# 01-PCIe.net
KiCad netlist of a schematic drawn in Altium Designer
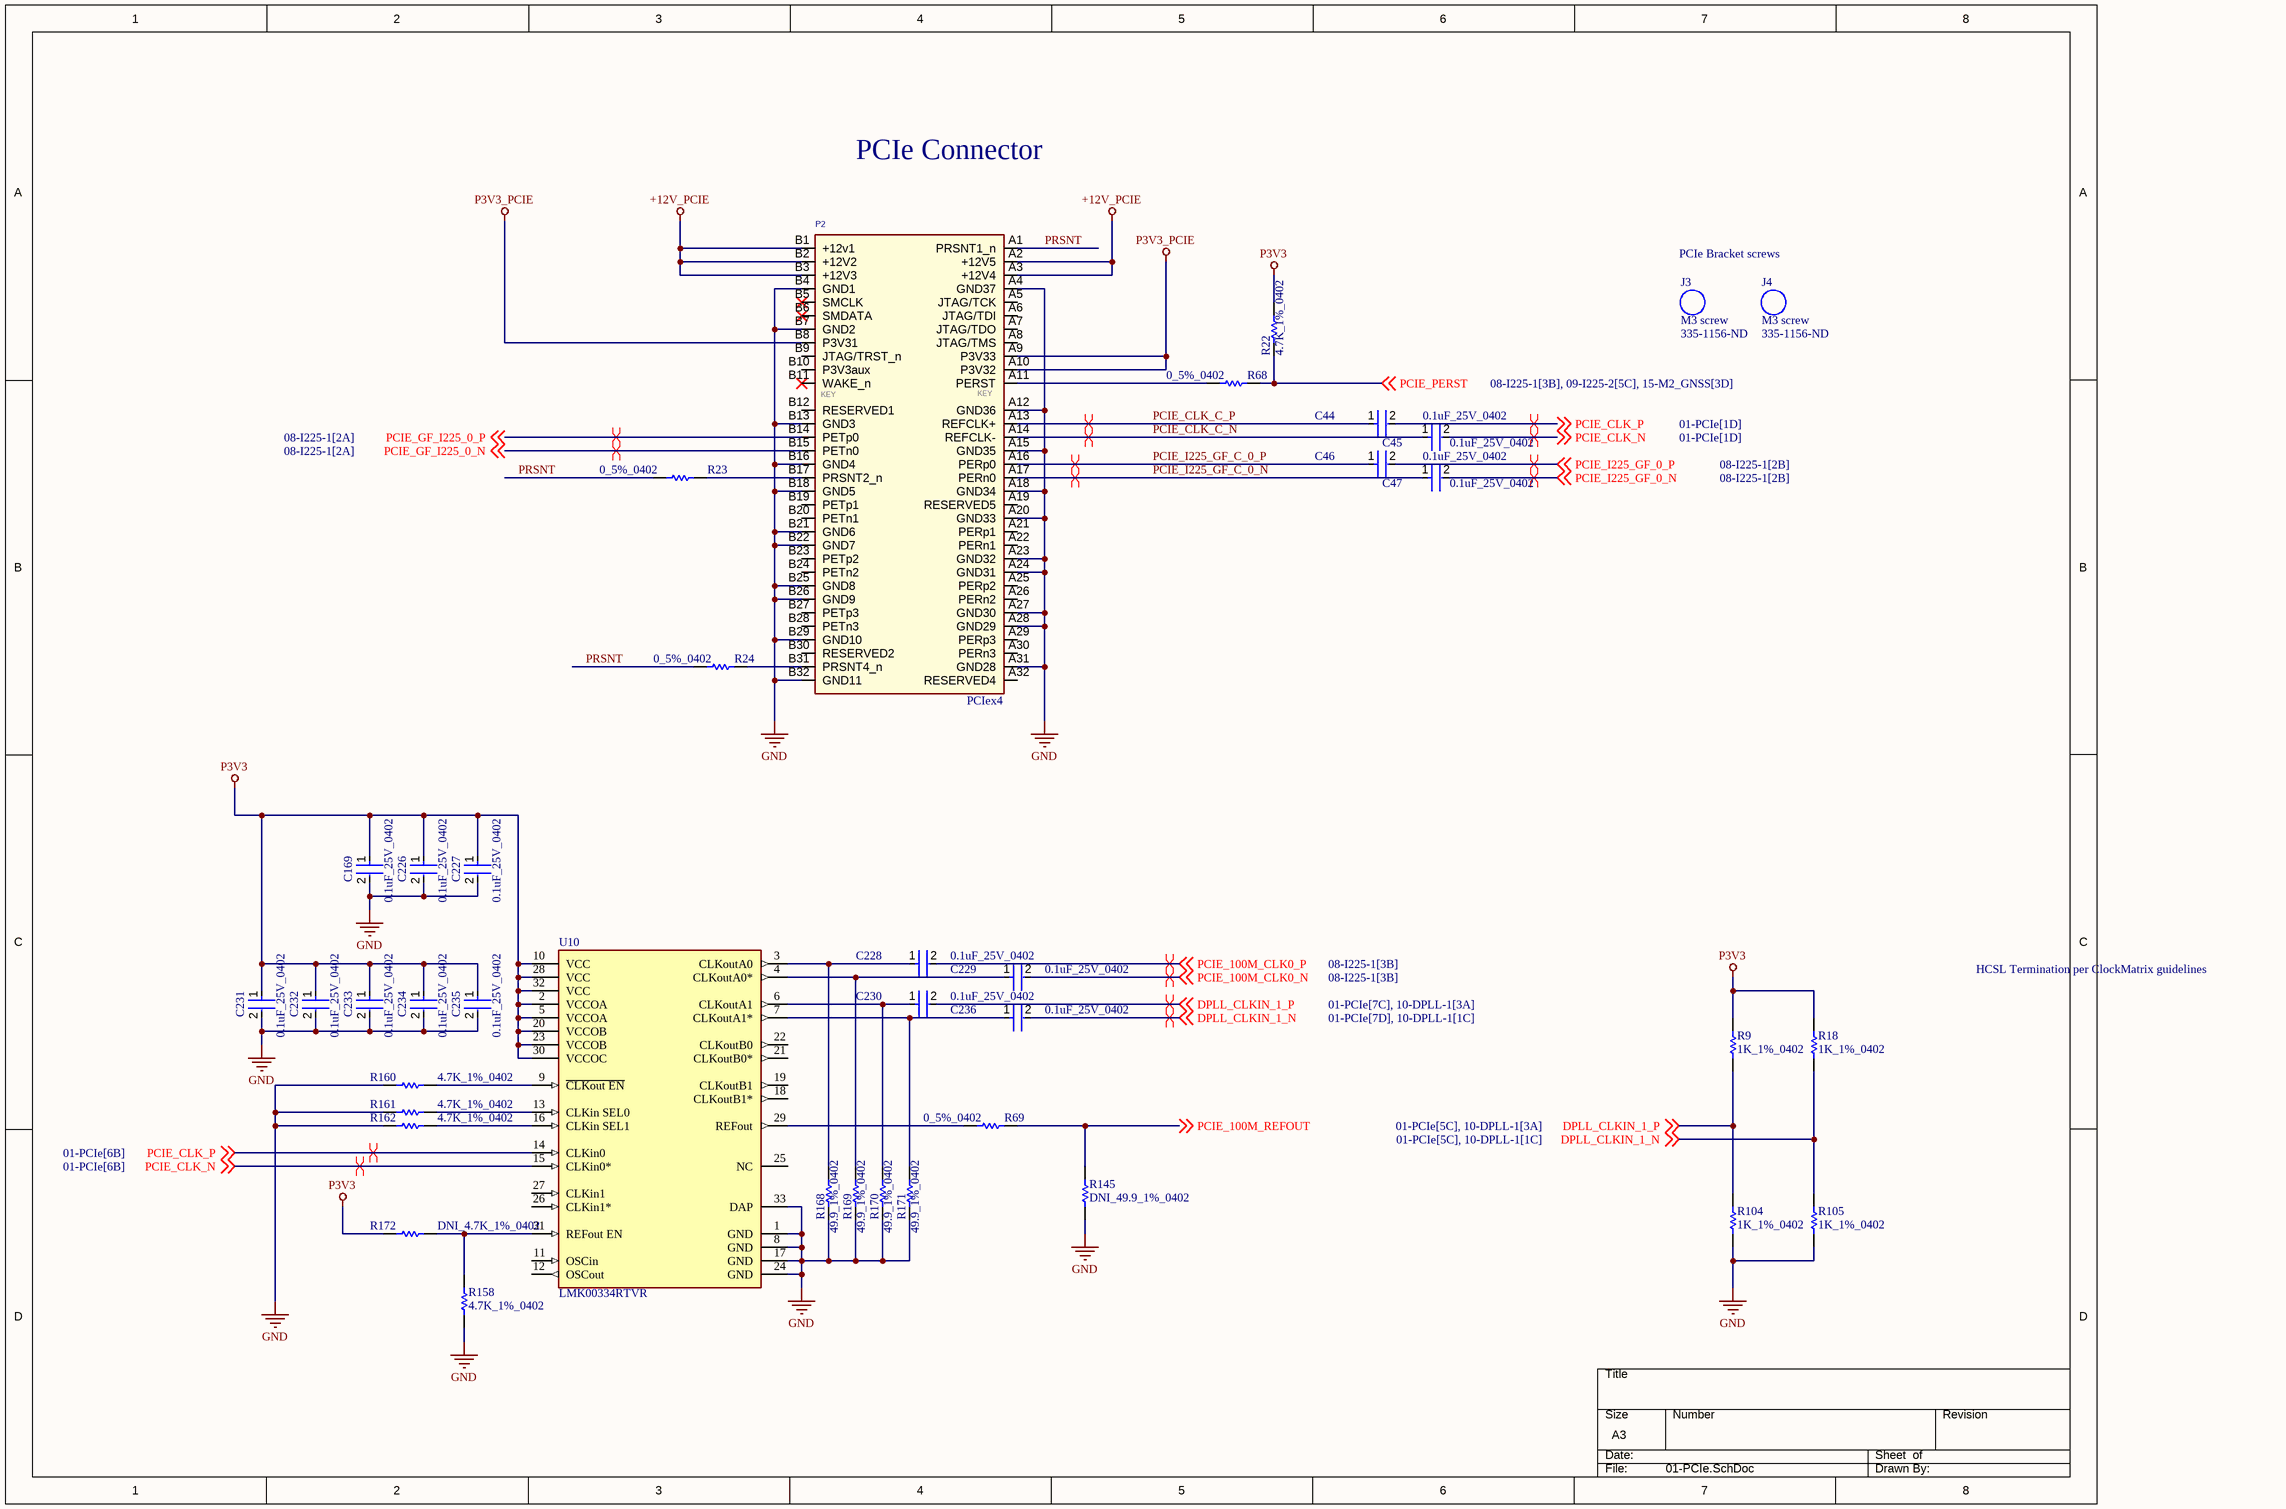
[diagram p0: 01-PCIe.SchDoc]

(export (version "E")
  (design (tool "Eeschema 10.0.6"))
  (components
    (comp (ref "C44")
      (value "0.1uF_25V_0402")
      (footprint "FP-0402-L_1_0_1-W_0_5_0_1-IPC_C")
      (description "General Purpose Ceramic Capacitor, 0402, 100nF, 10%, X7R, 15%, 25V")
      (fields (field (name "VOLTAGE") "25V") (field (name "TOLERANCE") "10%"))
      (libsource (lib "Altium Content Vault") (part "b4654b650e69147ec39a6b967a45e02"))
    )
    (comp (ref "C45")
      (value "0.1uF_25V_0402")
      (footprint "FP-0402-L_1_0_1-W_0_5_0_1-IPC_C")
      (description "General Purpose Ceramic Capacitor, 0402, 100nF, 10%, X7R, 15%, 25V")
      (fields (field (name "VOLTAGE") "25V") (field (name "TOLERANCE") "10%"))
      (libsource (lib "Altium Content Vault") (part "b4654b650e69147ec39a6b967a45e02"))
    )
    (comp (ref "C46")
      (value "0.1uF_25V_0402")
      (footprint "FP-0402-L_1_0_1-W_0_5_0_1-IPC_C")
      (description "General Purpose Ceramic Capacitor, 0402, 100nF, 10%, X7R, 15%, 25V")
      (fields (field (name "VOLTAGE") "25V") (field (name "TOLERANCE") "10%"))
      (libsource (lib "Altium Content Vault") (part "b4654b650e69147ec39a6b967a45e02"))
    )
    (comp (ref "C47")
      (value "0.1uF_25V_0402")
      (footprint "FP-0402-L_1_0_1-W_0_5_0_1-IPC_C")
      (description "General Purpose Ceramic Capacitor, 0402, 100nF, 10%, X7R, 15%, 25V")
      (fields (field (name "VOLTAGE") "25V") (field (name "TOLERANCE") "10%"))
      (libsource (lib "Altium Content Vault") (part "b4654b650e69147ec39a6b967a45e02"))
    )
    (comp (ref "C169")
      (value "0.1uF_25V_0402")
      (footprint "FP-0402-L_1_0_1-W_0_5_0_1-IPC_C")
      (description "General Purpose Ceramic Capacitor, 0402, 100nF, 10%, X7R, 15%, 25V")
      (fields (field (name "VOLTAGE") "25V") (field (name "TOLERANCE") "10%"))
      (libsource (lib "Altium Content Vault") (part "b4654b650e69147ec39a6b967a45e02"))
    )
    (comp (ref "C226")
      (value "0.1uF_25V_0402")
      (footprint "FP-0402-L_1_0_1-W_0_5_0_1-IPC_C")
      (description "General Purpose Ceramic Capacitor, 0402, 100nF, 10%, X7R, 15%, 25V")
      (fields (field (name "VOLTAGE") "25V") (field (name "TOLERANCE") "10%"))
      (libsource (lib "Altium Content Vault") (part "b4654b650e69147ec39a6b967a45e02"))
    )
    (comp (ref "C227")
      (value "0.1uF_25V_0402")
      (footprint "FP-0402-L_1_0_1-W_0_5_0_1-IPC_C")
      (description "General Purpose Ceramic Capacitor, 0402, 100nF, 10%, X7R, 15%, 25V")
      (fields (field (name "VOLTAGE") "25V") (field (name "TOLERANCE") "10%"))
      (libsource (lib "Altium Content Vault") (part "b4654b650e69147ec39a6b967a45e02"))
    )
    (comp (ref "C228")
      (value "0.1uF_25V_0402")
      (footprint "FP-0402-L_1_0_1-W_0_5_0_1-IPC_C")
      (description "General Purpose Ceramic Capacitor, 0402, 100nF, 10%, X7R, 15%, 25V")
      (fields (field (name "VOLTAGE") "25V") (field (name "TOLERANCE") "10%"))
      (libsource (lib "Altium Content Vault") (part "b4654b650e69147ec39a6b967a45e02"))
    )
    (comp (ref "C229")
      (value "0.1uF_25V_0402")
      (footprint "FP-0402-L_1_0_1-W_0_5_0_1-IPC_C")
      (description "General Purpose Ceramic Capacitor, 0402, 100nF, 10%, X7R, 15%, 25V")
      (fields (field (name "VOLTAGE") "25V") (field (name "TOLERANCE") "10%"))
      (libsource (lib "Altium Content Vault") (part "b4654b650e69147ec39a6b967a45e02"))
    )
    (comp (ref "C230")
      (value "0.1uF_25V_0402")
      (footprint "FP-0402-L_1_0_1-W_0_5_0_1-IPC_C")
      (description "General Purpose Ceramic Capacitor, 0402, 100nF, 10%, X7R, 15%, 25V")
      (fields (field (name "VOLTAGE") "25V") (field (name "TOLERANCE") "10%"))
      (libsource (lib "Altium Content Vault") (part "b4654b650e69147ec39a6b967a45e02"))
    )
    (comp (ref "C231")
      (value "0.1uF_25V_0402")
      (footprint "FP-0402-L_1_0_1-W_0_5_0_1-IPC_C")
      (description "General Purpose Ceramic Capacitor, 0402, 100nF, 10%, X7R, 15%, 25V")
      (fields (field (name "VOLTAGE") "25V") (field (name "TOLERANCE") "10%"))
      (libsource (lib "Altium Content Vault") (part "b4654b650e69147ec39a6b967a45e02"))
    )
    (comp (ref "C232")
      (value "0.1uF_25V_0402")
      (footprint "FP-0402-L_1_0_1-W_0_5_0_1-IPC_C")
      (description "General Purpose Ceramic Capacitor, 0402, 100nF, 10%, X7R, 15%, 25V")
      (fields (field (name "VOLTAGE") "25V") (field (name "TOLERANCE") "10%"))
      (libsource (lib "Altium Content Vault") (part "b4654b650e69147ec39a6b967a45e02"))
    )
    (comp (ref "C233")
      (value "0.1uF_25V_0402")
      (footprint "FP-0402-L_1_0_1-W_0_5_0_1-IPC_C")
      (description "General Purpose Ceramic Capacitor, 0402, 100nF, 10%, X7R, 15%, 25V")
      (fields (field (name "VOLTAGE") "25V") (field (name "TOLERANCE") "10%"))
      (libsource (lib "Altium Content Vault") (part "b4654b650e69147ec39a6b967a45e02"))
    )
    (comp (ref "C234")
      (value "0.1uF_25V_0402")
      (footprint "FP-0402-L_1_0_1-W_0_5_0_1-IPC_C")
      (description "General Purpose Ceramic Capacitor, 0402, 100nF, 10%, X7R, 15%, 25V")
      (fields (field (name "VOLTAGE") "25V") (field (name "TOLERANCE") "10%"))
      (libsource (lib "Altium Content Vault") (part "b4654b650e69147ec39a6b967a45e02"))
    )
    (comp (ref "C235")
      (value "0.1uF_25V_0402")
      (footprint "FP-0402-L_1_0_1-W_0_5_0_1-IPC_C")
      (description "General Purpose Ceramic Capacitor, 0402, 100nF, 10%, X7R, 15%, 25V")
      (fields (field (name "VOLTAGE") "25V") (field (name "TOLERANCE") "10%"))
      (libsource (lib "Altium Content Vault") (part "b4654b650e69147ec39a6b967a45e02"))
    )
    (comp (ref "C236")
      (value "0.1uF_25V_0402")
      (footprint "FP-0402-L_1_0_1-W_0_5_0_1-IPC_C")
      (description "General Purpose Ceramic Capacitor, 0402, 100nF, 10%, X7R, 15%, 25V")
      (fields (field (name "VOLTAGE") "25V") (field (name "TOLERANCE") "10%"))
      (libsource (lib "Altium Content Vault") (part "b4654b650e69147ec39a6b967a45e02"))
    )
    (comp (ref "J3")
      (value "M3 screw")
      (fields (field (name "SUPPLIER PART NUMBER 1") "335-1156-ND"))
      (libsource (lib "FPGA_CONN") (part "M3 screw"))
    )
    (comp (ref "J4")
      (value "M3 screw")
      (fields (field (name "SUPPLIER PART NUMBER 1") "335-1156-ND"))
      (libsource (lib "FPGA_CONN") (part "M3 screw"))
    )
    (comp (ref "P2")
      (value "PCIex4")
      (footprint "PCIE_4LANE_EDGE")
      (description "PCIE x4 Edge Connector,OrCAD Symbol,NC")
      (fields (field (name "PART NUMBER") "451") (field (name "MANUFACTURER") "NA"))
      (libsource (lib "Connectors") (part "PCIex4"))
    )
    (comp (ref "R9")
      (value "1K_1%_0402")
      (footprint "RESC1005X40X25NL05T05")
      (fields (field (name "MANUFACTURER") "Vishay Dale") (field (name "PART NUMBER") "CRCW04021K00FKTD"))
      (libsource (lib "Altium Content Vault") (part "RES"))
    )
    (comp (ref "R18")
      (value "1K_1%_0402")
      (footprint "RESC1005X40X25NL05T05")
      (fields (field (name "MANUFACTURER") "Vishay Dale") (field (name "PART NUMBER") "CRCW04021K00FKTD"))
      (libsource (lib "Altium Content Vault") (part "RES"))
    )
    (comp (ref "R22")
      (value "4.7K_1%_0402")
      (footprint "RESC1005X40X25NL10T10")
      (fields (field (name "MANUFACTURER") "Bourns") (field (name "PART NUMBER") "CR0402-FX-4701GLF"))
      (libsource (lib "Altium Content Vault") (part "RES"))
    )
    (comp (ref "R23")
      (value "0_5%_0402")
      (footprint "RESC1005X40X25LL10T10")
      (fields (field (name "MANUFACTURER") "KOA Speer") (field (name "PART NUMBER") "RK73Z1ETTP"))
      (libsource (lib "Altium Content Vault") (part "RES"))
    )
    (comp (ref "R24")
      (value "0_5%_0402")
      (footprint "RESC1005X40X25LL10T10")
      (fields (field (name "MANUFACTURER") "KOA Speer") (field (name "PART NUMBER") "RK73Z1ETTP"))
      (libsource (lib "Altium Content Vault") (part "RES"))
    )
    (comp (ref "R68")
      (value "0_5%_0402")
      (footprint "RESC1005X40X25LL10T10")
      (fields (field (name "MANUFACTURER") "KOA Speer") (field (name "PART NUMBER") "RK73Z1ETTP"))
      (libsource (lib "Altium Content Vault") (part "RES"))
    )
    (comp (ref "R69")
      (value "0_5%_0402")
      (footprint "RESC1005X40X25LL10T10")
      (fields (field (name "MANUFACTURER") "KOA Speer") (field (name "PART NUMBER") "RK73Z1ETTP"))
      (libsource (lib "Altium Content Vault") (part "RES"))
    )
    (comp (ref "R104")
      (value "1K_1%_0402")
      (footprint "RESC1005X40X25NL05T05")
      (fields (field (name "MANUFACTURER") "Vishay Dale") (field (name "PART NUMBER") "CRCW04021K00FKTD"))
      (libsource (lib "Altium Content Vault") (part "RES"))
    )
    (comp (ref "R105")
      (value "1K_1%_0402")
      (footprint "RESC1005X40X25NL05T05")
      (fields (field (name "MANUFACTURER") "Vishay Dale") (field (name "PART NUMBER") "CRCW04021K00FKTD"))
      (libsource (lib "Altium Content Vault") (part "RES"))
    )
    (comp (ref "R145")
      (value "DNI_49.9_1%_0402")
      (footprint "RESC1005X40X25NL10T10")
      (fields (field (name "PART NUMBER") "RK73H1ETTP49R9F") (field (name "MANUFACTURER") "KOA Speer"))
      (libsource (lib "Altium Content Vault") (part "RES"))
    )
    (comp (ref "R158")
      (value "4.7K_1%_0402")
      (footprint "RESC1005X40X25NL10T10")
      (fields (field (name "MANUFACTURER") "Bourns") (field (name "PART NUMBER") "CR0402-FX-4701GLF"))
      (libsource (lib "Altium Content Vault") (part "RES"))
    )
    (comp (ref "R160")
      (value "4.7K_1%_0402")
      (footprint "RESC1005X40X25NL10T10")
      (fields (field (name "MANUFACTURER") "Bourns") (field (name "PART NUMBER") "CR0402-FX-4701GLF"))
      (libsource (lib "Altium Content Vault") (part "RES"))
    )
    (comp (ref "R161")
      (value "4.7K_1%_0402")
      (footprint "RESC1005X40X25NL10T10")
      (fields (field (name "MANUFACTURER") "Bourns") (field (name "PART NUMBER") "CR0402-FX-4701GLF"))
      (libsource (lib "Altium Content Vault") (part "RES"))
    )
    (comp (ref "R162")
      (value "4.7K_1%_0402")
      (footprint "RESC1005X40X25NL10T10")
      (fields (field (name "MANUFACTURER") "Bourns") (field (name "PART NUMBER") "CR0402-FX-4701GLF"))
      (libsource (lib "Altium Content Vault") (part "RES"))
    )
    (comp (ref "R168")
      (value "49.9_1%_0402")
      (footprint "RESC1005X40X25NL10T10")
      (fields (field (name "PART NUMBER") "RK73H1ETTP49R9F") (field (name "MANUFACTURER") "KOA Speer"))
      (libsource (lib "Altium Content Vault") (part "RES"))
    )
    (comp (ref "R169")
      (value "49.9_1%_0402")
      (footprint "RESC1005X40X25NL10T10")
      (fields (field (name "PART NUMBER") "RK73H1ETTP49R9F") (field (name "MANUFACTURER") "KOA Speer"))
      (libsource (lib "Altium Content Vault") (part "RES"))
    )
    (comp (ref "R170")
      (value "49.9_1%_0402")
      (footprint "RESC1005X40X25NL10T10")
      (fields (field (name "PART NUMBER") "RK73H1ETTP49R9F") (field (name "MANUFACTURER") "KOA Speer"))
      (libsource (lib "Altium Content Vault") (part "RES"))
    )
    (comp (ref "R171")
      (value "49.9_1%_0402")
      (footprint "RESC1005X40X25NL10T10")
      (fields (field (name "PART NUMBER") "RK73H1ETTP49R9F") (field (name "MANUFACTURER") "KOA Speer"))
      (libsource (lib "Altium Content Vault") (part "RES"))
    )
    (comp (ref "R172")
      (value "DNI_4.7K_1%_0402")
      (footprint "RESC1005X40X25NL10T10")
      (fields (field (name "MANUFACTURER") "Bourns") (field (name "PART NUMBER") "CR0402-FX-4701GLF"))
      (libsource (lib "Altium Content Vault") (part "RES"))
    )
    (comp (ref "U10")
      (value "LMK00334RTVR")
      (footprint "FP-RTV0032A-MFG")
      (description "IC CLK BUF 400MHZ 1CIRC 32WQFN")
      (libsource (lib "Altium Content Vault") (part "b0788d09999557299357136416a342e"))
    )
  )
  (nets
    (net (code "1") (name "+12V_PCIE") (class "Default")
      (node (ref "P2") (pin "A2") (pinfunction "+12V5_A2") (pintype "passive"))
      (node (ref "P2") (pin "A3") (pinfunction "+12V4_A3") (pintype "passive"))
      (node (ref "P2") (pin "B1") (pinfunction "+12v1_B1") (pintype "power_in"))
      (node (ref "P2") (pin "B2") (pinfunction "+12V2_B2") (pintype "power_in"))
      (node (ref "P2") (pin "B3") (pinfunction "+12V3_B3") (pintype "power_in"))
    )
    (net (code "2") (name "/PCIE_CLK_C_N") (class "Default")
      (node (ref "C45") (pin "1") (pinfunction "1_1") (pintype "passive"))
      (node (ref "P2") (pin "A14") (pinfunction "REFCLK-_A14") (pintype "passive"))
    )
    (net (code "3") (name "/PCIE_CLK_C_P") (class "Default")
      (node (ref "C44") (pin "1") (pinfunction "1_1") (pintype "passive"))
      (node (ref "P2") (pin "A13") (pinfunction "REFCLK+_A13") (pintype "passive"))
    )
    (net (code "4") (name "/PCIE_I225_GF_C_0_N") (class "Default")
      (node (ref "C47") (pin "1") (pinfunction "1_1") (pintype "passive"))
      (node (ref "P2") (pin "A17") (pinfunction "PERn0_A17") (pintype "passive"))
    )
    (net (code "5") (name "/PCIE_I225_GF_C_0_P") (class "Default")
      (node (ref "C46") (pin "1") (pinfunction "1_1") (pintype "passive"))
      (node (ref "P2") (pin "A16") (pinfunction "PERp0_A16") (pintype "passive"))
    )
    (net (code "6") (name "/PRSNT") (class "Default")
      (node (ref "P2") (pin "A1") (pinfunction "PRSNT1_n_A1") (pintype "passive"))
      (node (ref "R23") (pin "1") (pinfunction "1_1") (pintype "passive"))
      (node (ref "R24") (pin "1") (pinfunction "1_1") (pintype "passive"))
    )
    (net (code "7") (name "DPLL_CLKIN_1_N") (class "Default")
      (node (ref "C236") (pin "2") (pinfunction "2_2") (pintype "passive"))
      (node (ref "R105") (pin "2") (pinfunction "2_2") (pintype "passive"))
      (node (ref "R18") (pin "1") (pinfunction "1_1") (pintype "passive"))
    )
    (net (code "8") (name "DPLL_CLKIN_1_P") (class "Default")
      (node (ref "C230") (pin "2") (pinfunction "2_2") (pintype "passive"))
      (node (ref "R104") (pin "2") (pinfunction "2_2") (pintype "passive"))
      (node (ref "R9") (pin "1") (pinfunction "1_1") (pintype "passive"))
    )
    (net (code "9") (name "GND") (class "Default")
      (node (ref "C169") (pin "2") (pinfunction "2_2") (pintype "passive"))
      (node (ref "C226") (pin "2") (pinfunction "2_2") (pintype "passive"))
      (node (ref "C227") (pin "2") (pinfunction "2_2") (pintype "passive"))
      (node (ref "C231") (pin "2") (pinfunction "2_2") (pintype "passive"))
      (node (ref "C232") (pin "2") (pinfunction "2_2") (pintype "passive"))
      (node (ref "C233") (pin "2") (pinfunction "2_2") (pintype "passive"))
      (node (ref "C234") (pin "2") (pinfunction "2_2") (pintype "passive"))
      (node (ref "C235") (pin "2") (pinfunction "2_2") (pintype "passive"))
      (node (ref "P2") (pin "A12") (pinfunction "GND36_A12") (pintype "power_in"))
      (node (ref "P2") (pin "A15") (pinfunction "GND35_A15") (pintype "power_in"))
      (node (ref "P2") (pin "A18") (pinfunction "GND34_A18") (pintype "power_in"))
      (node (ref "P2") (pin "A20") (pinfunction "GND33_A20") (pintype "power_in"))
      (node (ref "P2") (pin "A23") (pinfunction "GND32_A23") (pintype "power_in"))
      (node (ref "P2") (pin "A24") (pinfunction "GND31_A24") (pintype "power_in"))
      (node (ref "P2") (pin "A27") (pinfunction "GND30_A27") (pintype "power_in"))
      (node (ref "P2") (pin "A28") (pinfunction "GND29_A28") (pintype "power_in"))
      (node (ref "P2") (pin "A31") (pinfunction "GND28_A31") (pintype "power_in"))
      (node (ref "P2") (pin "A4") (pinfunction "GND37_A4") (pintype "power_in"))
      (node (ref "P2") (pin "B13") (pinfunction "GND3_B13") (pintype "power_in"))
      (node (ref "P2") (pin "B16") (pinfunction "GND4_B16") (pintype "power_in"))
      (node (ref "P2") (pin "B18") (pinfunction "GND5_B18") (pintype "power_in"))
      (node (ref "P2") (pin "B21") (pinfunction "GND6_B21") (pintype "power_in"))
      (node (ref "P2") (pin "B22") (pinfunction "GND7_B22") (pintype "power_in"))
      (node (ref "P2") (pin "B25") (pinfunction "GND8_B25") (pintype "power_in"))
      (node (ref "P2") (pin "B26") (pinfunction "GND9_B26") (pintype "power_in"))
      (node (ref "P2") (pin "B29") (pinfunction "GND10_B29") (pintype "power_in"))
      (node (ref "P2") (pin "B32") (pinfunction "GND11_B32") (pintype "power_in"))
      (node (ref "P2") (pin "B4") (pinfunction "GND1_B4") (pintype "power_in"))
      (node (ref "P2") (pin "B7") (pinfunction "GND2_B7") (pintype "power_in"))
      (node (ref "R104") (pin "1") (pinfunction "1_1") (pintype "passive"))
      (node (ref "R105") (pin "1") (pinfunction "1_1") (pintype "passive"))
      (node (ref "R145") (pin "2") (pinfunction "2_2") (pintype "passive"))
      (node (ref "R158") (pin "2") (pinfunction "2_2") (pintype "passive"))
      (node (ref "R160") (pin "2") (pinfunction "2_2") (pintype "passive"))
      (node (ref "R161") (pin "2") (pinfunction "2_2") (pintype "passive"))
      (node (ref "R162") (pin "2") (pinfunction "2_2") (pintype "passive"))
      (node (ref "R168") (pin "1") (pinfunction "1_1") (pintype "passive"))
      (node (ref "R169") (pin "1") (pinfunction "1_1") (pintype "passive"))
      (node (ref "R170") (pin "1") (pinfunction "1_1") (pintype "passive"))
      (node (ref "R171") (pin "1") (pinfunction "1_1") (pintype "passive"))
      (node (ref "U10") (pin "1") (pinfunction "GND_1") (pintype "power_in"))
      (node (ref "U10") (pin "17") (pinfunction "GND_17") (pintype "power_in"))
      (node (ref "U10") (pin "24") (pinfunction "GND_24") (pintype "power_in"))
      (node (ref "U10") (pin "33") (pinfunction "DAP_33") (pintype "power_in"))
      (node (ref "U10") (pin "8") (pinfunction "GND_8") (pintype "power_in"))
    )
    (net (code "10") (name "Net-(P2-PERST)") (class "Default")
      (node (ref "P2") (pin "A11") (pinfunction "PERST_A11") (pintype "passive"))
      (node (ref "R68") (pin "1") (pinfunction "1_1") (pintype "passive"))
    )
    (net (code "11") (name "Net-(P2-PRSNT2_n)") (class "Default")
      (node (ref "P2") (pin "B17") (pinfunction "PRSNT2_n_B17") (pintype "passive"))
      (node (ref "R23") (pin "2") (pinfunction "2_2") (pintype "passive"))
    )
    (net (code "12") (name "Net-(P2-PRSNT4_n)") (class "Default")
      (node (ref "P2") (pin "B31") (pinfunction "PRSNT4_n_B31") (pintype "passive"))
      (node (ref "R24") (pin "2") (pinfunction "2_2") (pintype "passive"))
    )
    (net (code "13") (name "Net-(U10-CLKin_SEL0)") (class "Default")
      (node (ref "R161") (pin "1") (pinfunction "1_1") (pintype "passive"))
      (node (ref "U10") (pin "13") (pinfunction "CLKin_SEL0_13") (pintype "input"))
    )
    (net (code "14") (name "Net-(U10-CLKin_SEL1)") (class "Default")
      (node (ref "R162") (pin "1") (pinfunction "1_1") (pintype "passive"))
      (node (ref "U10") (pin "16") (pinfunction "CLKin_SEL1_16") (pintype "input"))
    )
    (net (code "15") (name "Net-(U10-CLKoutA0)") (class "Default")
      (node (ref "C228") (pin "1") (pinfunction "1_1") (pintype "passive"))
      (node (ref "R168") (pin "2") (pinfunction "2_2") (pintype "passive"))
      (node (ref "U10") (pin "3") (pinfunction "CLKoutA0_3") (pintype "output"))
    )
    (net (code "16") (name "Net-(U10-CLKoutA0*)") (class "Default")
      (node (ref "C229") (pin "1") (pinfunction "1_1") (pintype "passive"))
      (node (ref "R169") (pin "2") (pinfunction "2_2") (pintype "passive"))
      (node (ref "U10") (pin "4") (pinfunction "CLKoutA0*_4") (pintype "output"))
    )
    (net (code "17") (name "Net-(U10-CLKoutA1)") (class "Default")
      (node (ref "C230") (pin "1") (pinfunction "1_1") (pintype "passive"))
      (node (ref "R170") (pin "2") (pinfunction "2_2") (pintype "passive"))
      (node (ref "U10") (pin "6") (pinfunction "CLKoutA1_6") (pintype "output"))
    )
    (net (code "18") (name "Net-(U10-CLKoutA1*)") (class "Default")
      (node (ref "C236") (pin "1") (pinfunction "1_1") (pintype "passive"))
      (node (ref "R171") (pin "2") (pinfunction "2_2") (pintype "passive"))
      (node (ref "U10") (pin "7") (pinfunction "CLKoutA1*_7") (pintype "output"))
    )
    (net (code "19") (name "Net-(U10-REFout)") (class "Default")
      (node (ref "R69") (pin "1") (pinfunction "1_1") (pintype "passive"))
      (node (ref "U10") (pin "29") (pinfunction "REFout_29") (pintype "output"))
    )
    (net (code "20") (name "Net-(U10-REFout_EN)") (class "Default")
      (node (ref "R158") (pin "1") (pinfunction "1_1") (pintype "passive"))
      (node (ref "R172") (pin "1") (pinfunction "1_1") (pintype "passive"))
      (node (ref "U10") (pin "31") (pinfunction "REFout_EN_31") (pintype "input"))
    )
    (net (code "21") (name "Net-(U10-~{CLKout_EN})") (class "Default")
      (node (ref "R160") (pin "1") (pinfunction "1_1") (pintype "passive"))
      (node (ref "U10") (pin "9") (pinfunction "~{CLKout_EN}_9") (pintype "input"))
    )
    (net (code "22") (name "P3V3") (class "Default")
      (node (ref "C169") (pin "1") (pinfunction "1_1") (pintype "passive"))
      (node (ref "C226") (pin "1") (pinfunction "1_1") (pintype "passive"))
      (node (ref "C227") (pin "1") (pinfunction "1_1") (pintype "passive"))
      (node (ref "C231") (pin "1") (pinfunction "1_1") (pintype "passive"))
      (node (ref "C232") (pin "1") (pinfunction "1_1") (pintype "passive"))
      (node (ref "C233") (pin "1") (pinfunction "1_1") (pintype "passive"))
      (node (ref "C234") (pin "1") (pinfunction "1_1") (pintype "passive"))
      (node (ref "C235") (pin "1") (pinfunction "1_1") (pintype "passive"))
      (node (ref "R172") (pin "2") (pinfunction "2_2") (pintype "passive"))
      (node (ref "R18") (pin "2") (pinfunction "2_2") (pintype "passive"))
      (node (ref "R22") (pin "2") (pinfunction "2_2") (pintype "passive"))
      (node (ref "R9") (pin "2") (pinfunction "2_2") (pintype "passive"))
      (node (ref "U10") (pin "10") (pinfunction "VCC_10") (pintype "power_in"))
      (node (ref "U10") (pin "2") (pinfunction "VCCOA_2") (pintype "power_in"))
      (node (ref "U10") (pin "20") (pinfunction "VCCOB_20") (pintype "power_in"))
      (node (ref "U10") (pin "23") (pinfunction "VCCOB_23") (pintype "power_in"))
      (node (ref "U10") (pin "28") (pinfunction "VCC_28") (pintype "power_in"))
      (node (ref "U10") (pin "30") (pinfunction "VCCOC_30") (pintype "power_in"))
      (node (ref "U10") (pin "32") (pinfunction "VCC_32") (pintype "power_in"))
      (node (ref "U10") (pin "5") (pinfunction "VCCOA_5") (pintype "power_in"))
    )
    (net (code "23") (name "P3V3_PCIE") (class "Default")
      (node (ref "P2") (pin "A10") (pinfunction "P3V32_A10") (pintype "passive"))
      (node (ref "P2") (pin "A9") (pinfunction "P3V33_A9") (pintype "passive"))
      (node (ref "P2") (pin "B8") (pinfunction "P3V31_B8") (pintype "power_in"))
    )
    (net (code "24") (name "PCIE_100M_CLK0_N") (class "Default")
      (node (ref "C229") (pin "2") (pinfunction "2_2") (pintype "passive"))
    )
    (net (code "25") (name "PCIE_100M_CLK0_P") (class "Default")
      (node (ref "C228") (pin "2") (pinfunction "2_2") (pintype "passive"))
    )
    (net (code "26") (name "PCIE_100M_REFOUT") (class "Default")
      (node (ref "R145") (pin "1") (pinfunction "1_1") (pintype "passive"))
      (node (ref "R69") (pin "2") (pinfunction "2_2") (pintype "passive"))
    )
    (net (code "27") (name "PCIE_CLK_N") (class "Default")
      (node (ref "C45") (pin "2") (pinfunction "2_2") (pintype "passive"))
      (node (ref "U10") (pin "15") (pinfunction "CLKin0*_15") (pintype "input"))
    )
    (net (code "28") (name "PCIE_CLK_P") (class "Default")
      (node (ref "C44") (pin "2") (pinfunction "2_2") (pintype "passive"))
      (node (ref "U10") (pin "14") (pinfunction "CLKin0_14") (pintype "input"))
    )
    (net (code "29") (name "PCIE_GF_I225_0_N") (class "Default")
      (node (ref "P2") (pin "B15") (pinfunction "PETn0_B15") (pintype "passive"))
    )
    (net (code "30") (name "PCIE_GF_I225_0_P") (class "Default")
      (node (ref "P2") (pin "B14") (pinfunction "PETp0_B14") (pintype "passive"))
    )
    (net (code "31") (name "PCIE_I225_GF_0_N") (class "Default")
      (node (ref "C47") (pin "2") (pinfunction "2_2") (pintype "passive"))
    )
    (net (code "32") (name "PCIE_I225_GF_0_P") (class "Default")
      (node (ref "C46") (pin "2") (pinfunction "2_2") (pintype "passive"))
    )
    (net (code "33") (name "PCIE_PERST") (class "Default")
      (node (ref "R22") (pin "1") (pinfunction "1_1") (pintype "passive"))
      (node (ref "R68") (pin "2") (pinfunction "2_2") (pintype "passive"))
    )
    (net (code "34") (name "unconnected-(P2-JTAG{slash}TCK-PadA5)") (class "Default")
      (node (ref "P2") (pin "A5") (pinfunction "JTAG/TCK_A5") (pintype "passive"))
    )
    (net (code "35") (name "unconnected-(P2-JTAG{slash}TDI-PadA6)") (class "Default")
      (node (ref "P2") (pin "A6") (pinfunction "JTAG/TDI_A6") (pintype "passive"))
    )
    (net (code "36") (name "unconnected-(P2-JTAG{slash}TDO-PadA7)") (class "Default")
      (node (ref "P2") (pin "A7") (pinfunction "JTAG/TDO_A7") (pintype "passive"))
    )
    (net (code "37") (name "unconnected-(P2-JTAG{slash}TMS-PadA8)") (class "Default")
      (node (ref "P2") (pin "A8") (pinfunction "JTAG/TMS_A8") (pintype "passive"))
    )
    (net (code "38") (name "unconnected-(P2-JTAG{slash}TRST_n-PadB9)") (class "Default")
      (node (ref "P2") (pin "B9") (pinfunction "JTAG/TRST_n_B9") (pintype "passive"))
    )
    (net (code "39") (name "unconnected-(P2-P3V3aux-PadB10)") (class "Default")
      (node (ref "P2") (pin "B10") (pinfunction "P3V3aux_B10") (pintype "passive"))
    )
    (net (code "40") (name "unconnected-(P2-PERn1-PadA22)") (class "Default")
      (node (ref "P2") (pin "A22") (pinfunction "PERn1_A22") (pintype "passive"))
    )
    (net (code "41") (name "unconnected-(P2-PERn2-PadA26)") (class "Default")
      (node (ref "P2") (pin "A26") (pinfunction "PERn2_A26") (pintype "passive"))
    )
    (net (code "42") (name "unconnected-(P2-PERn3-PadA30)") (class "Default")
      (node (ref "P2") (pin "A30") (pinfunction "PERn3_A30") (pintype "passive"))
    )
    (net (code "43") (name "unconnected-(P2-PERp1-PadA21)") (class "Default")
      (node (ref "P2") (pin "A21") (pinfunction "PERp1_A21") (pintype "passive"))
    )
    (net (code "44") (name "unconnected-(P2-PERp2-PadA25)") (class "Default")
      (node (ref "P2") (pin "A25") (pinfunction "PERp2_A25") (pintype "passive"))
    )
    (net (code "45") (name "unconnected-(P2-PERp3-PadA29)") (class "Default")
      (node (ref "P2") (pin "A29") (pinfunction "PERp3_A29") (pintype "passive"))
    )
    (net (code "46") (name "unconnected-(P2-PETn1-PadB20)") (class "Default")
      (node (ref "P2") (pin "B20") (pinfunction "PETn1_B20") (pintype "passive"))
    )
    (net (code "47") (name "unconnected-(P2-PETn2-PadB24)") (class "Default")
      (node (ref "P2") (pin "B24") (pinfunction "PETn2_B24") (pintype "passive"))
    )
    (net (code "48") (name "unconnected-(P2-PETn3-PadB28)") (class "Default")
      (node (ref "P2") (pin "B28") (pinfunction "PETn3_B28") (pintype "passive"))
    )
    (net (code "49") (name "unconnected-(P2-PETp1-PadB19)") (class "Default")
      (node (ref "P2") (pin "B19") (pinfunction "PETp1_B19") (pintype "passive"))
    )
    (net (code "50") (name "unconnected-(P2-PETp2-PadB23)") (class "Default")
      (node (ref "P2") (pin "B23") (pinfunction "PETp2_B23") (pintype "passive"))
    )
    (net (code "51") (name "unconnected-(P2-PETp3-PadB27)") (class "Default")
      (node (ref "P2") (pin "B27") (pinfunction "PETp3_B27") (pintype "passive"))
    )
    (net (code "52") (name "unconnected-(P2-RESERVED1-PadB12)") (class "Default")
      (node (ref "P2") (pin "B12") (pinfunction "RESERVED1_B12") (pintype "passive"))
    )
    (net (code "53") (name "unconnected-(P2-RESERVED2-PadB30)") (class "Default")
      (node (ref "P2") (pin "B30") (pinfunction "RESERVED2_B30") (pintype "passive"))
    )
    (net (code "54") (name "unconnected-(P2-RESERVED4-PadA32)") (class "Default")
      (node (ref "P2") (pin "A32") (pinfunction "RESERVED4_A32") (pintype "passive"))
    )
    (net (code "55") (name "unconnected-(P2-RESERVED5-PadA19)") (class "Default")
      (node (ref "P2") (pin "A19") (pinfunction "RESERVED5_A19") (pintype "passive"))
    )
    (net (code "56") (name "unconnected-(P2-SMCLK-PadB5)") (class "Default")
      (node (ref "P2") (pin "B5") (pinfunction "SMCLK_B5") (pintype "passive+no_connect"))
    )
    (net (code "57") (name "unconnected-(P2-SMDATA-PadB6)") (class "Default")
      (node (ref "P2") (pin "B6") (pinfunction "SMDATA_B6") (pintype "passive+no_connect"))
    )
    (net (code "58") (name "unconnected-(P2-WAKE_n-PadB11)") (class "Default")
      (node (ref "P2") (pin "B11") (pinfunction "WAKE_n_B11") (pintype "passive+no_connect"))
    )
    (net (code "59") (name "unconnected-(U10-CLKin1*-Pad26)") (class "Default")
      (node (ref "U10") (pin "26") (pinfunction "CLKin1*_26") (pintype "input"))
    )
    (net (code "60") (name "unconnected-(U10-CLKin1-Pad27)") (class "Default")
      (node (ref "U10") (pin "27") (pinfunction "CLKin1_27") (pintype "input"))
    )
    (net (code "61") (name "unconnected-(U10-CLKoutB0*-Pad21)") (class "Default")
      (node (ref "U10") (pin "21") (pinfunction "CLKoutB0*_21") (pintype "output"))
    )
    (net (code "62") (name "unconnected-(U10-CLKoutB0-Pad22)") (class "Default")
      (node (ref "U10") (pin "22") (pinfunction "CLKoutB0_22") (pintype "output"))
    )
    (net (code "63") (name "unconnected-(U10-CLKoutB1*-Pad18)") (class "Default")
      (node (ref "U10") (pin "18") (pinfunction "CLKoutB1*_18") (pintype "output"))
    )
    (net (code "64") (name "unconnected-(U10-CLKoutB1-Pad19)") (class "Default")
      (node (ref "U10") (pin "19") (pinfunction "CLKoutB1_19") (pintype "output"))
    )
    (net (code "65") (name "unconnected-(U10-NC-Pad25)") (class "Default")
      (node (ref "U10") (pin "25") (pinfunction "NC_25") (pintype "passive"))
    )
    (net (code "66") (name "unconnected-(U10-OSCin-Pad11)") (class "Default")
      (node (ref "U10") (pin "11") (pinfunction "OSCin_11") (pintype "input"))
    )
    (net (code "67") (name "unconnected-(U10-OSCout-Pad12)") (class "Default")
      (node (ref "U10") (pin "12") (pinfunction "OSCout_12") (pintype "output"))
    )
  )
)
